# SCH_ESP32-Radio_2026-02-18.net
KiCad netlist of a schematic drawn in EasyEDA
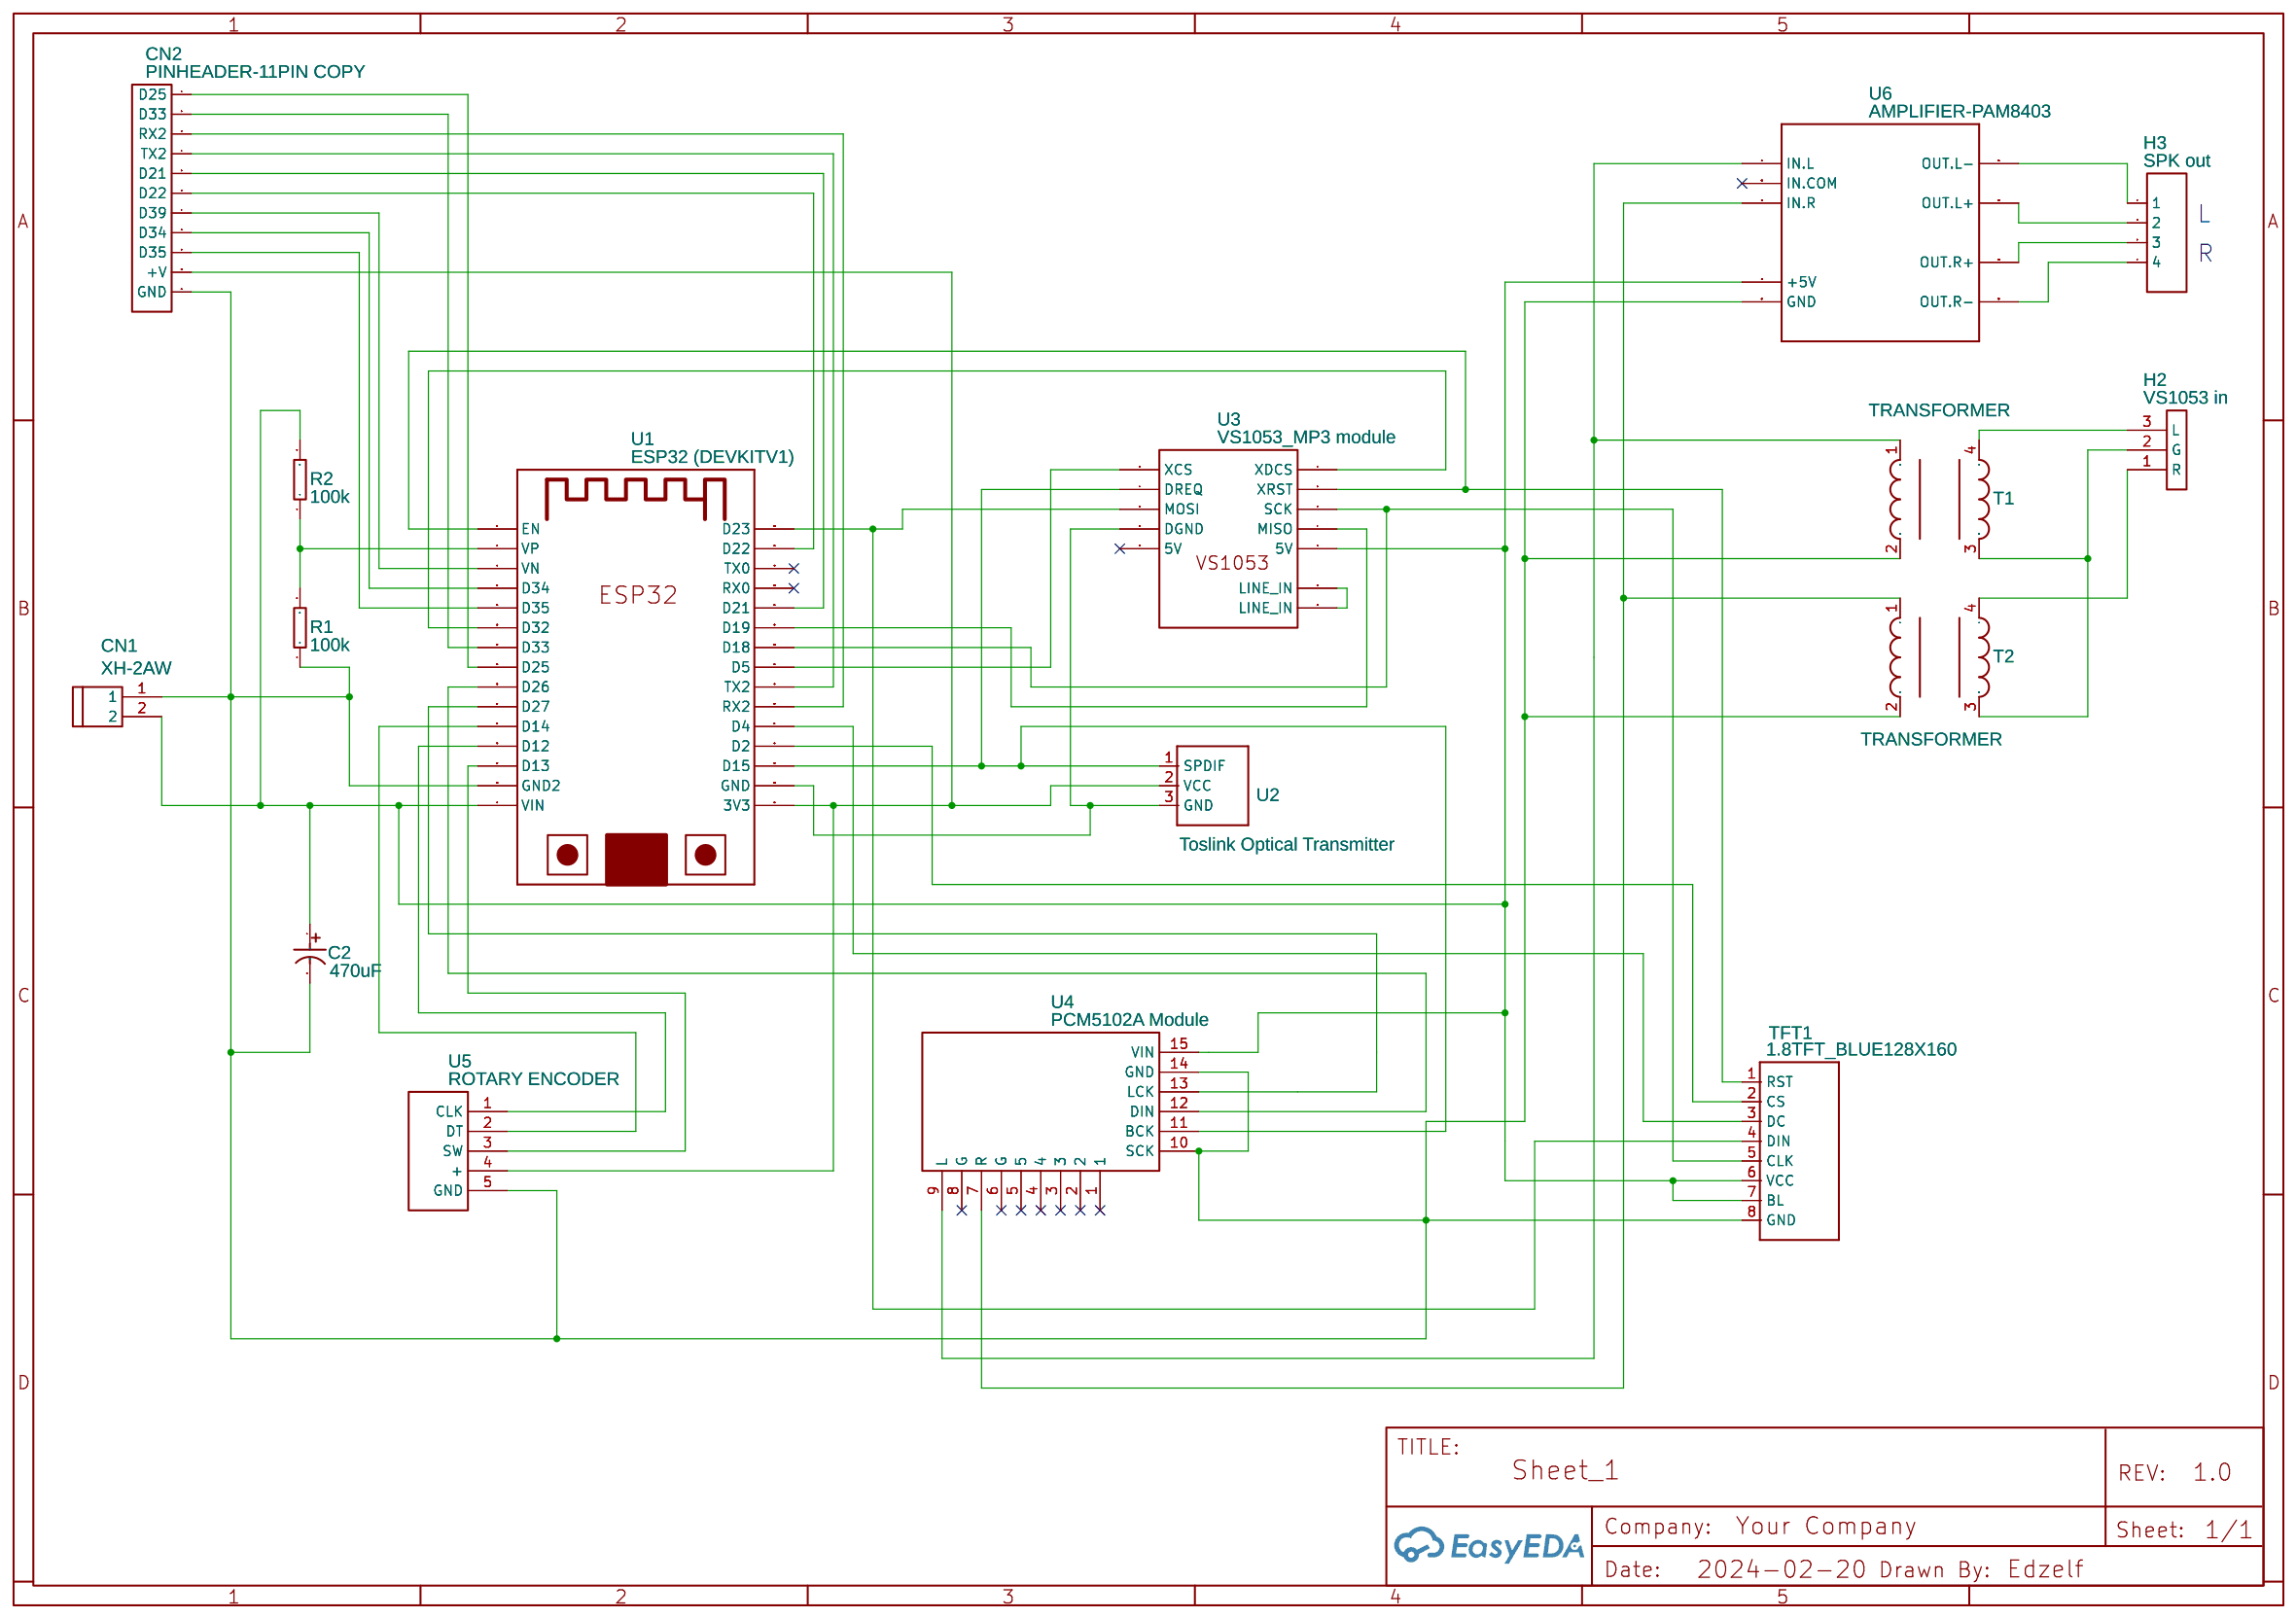
[diagram p0: schematic sheet]

(export (version "E")
  (design (tool "Eeschema 10.0.6"))
  (components
    (comp (ref "C2")
      (value "470uF")
      (fields (field (name "Manufacturer Part") "470uF 25V 8*14") (field (name "Manufacturer") "ValuePro"))
      (libsource (lib "") (part "470UF 25V 8X14"))
    )
    (comp (ref "CN1")
      (value "XH-2AW")
      (fields (field (name "Manufacturer") "BOOMELE(博穆精密)"))
      (libsource (lib "") (part "XH-2AW"))
    )
    (comp (ref "CN2") (value "PINHEADER-11PIN COPY") (libsource (lib "") (part "PINHEADER-11PIN COPY")))
    (comp (ref "H2") (value "VS1053 in") (libsource (lib "") (part "Pins_header1*3")))
    (comp (ref "H3")
      (value "SPK out")
      (fields
        (field (name "Manufacturer Part") "Female headerHDR1X8-2.54")
        (field (name "Manufacturer") "BOOMELE")
      )
      (libsource (lib "") (part "HEADER 4 PINS"))
    )
    (comp (ref "R1") (value "100k") (libsource (lib "") (part "Resistor 0.5W")))
    (comp (ref "R2") (value "100k") (libsource (lib "") (part "Resistor 0.5W")))
    (comp (ref "T1") (value "TRANSFORMER") (libsource (lib "") (part "TRANSFORMER")))
    (comp (ref "T2") (value "TRANSFORMER") (libsource (lib "") (part "TRANSFORMER")))
    (comp (ref "TFT1") (value "1.8TFT_BLUE128X160") (libsource (lib "") (part "1.8TFT_BLUE128X160")))
    (comp (ref "U1") (value "ESP32 (DEVKITV1)") (libsource (lib "") (part "ESP32-DEVKIT-V1-30PIN")))
    (comp (ref "U2")
      (value "Toslink Optical Transmitter")
      (fields (field (name "Manufacturer Part") "TOTX178A") (field (name "Manufacturer") "Toshiba"))
      (libsource (lib "") (part "TOTX178A Toslink Optical Transmitter"))
    )
    (comp (ref "U3")
      (value "VS1053_MP3 module")
      (fields (field (name "Manufacturer Part") "VS1053"))
      (libsource (lib "") (part "VS1053_MODULO_MP3"))
    )
    (comp (ref "U4") (value "PCM5102A Module") (libsource (lib "") (part "PCM5102A Module")))
    (comp (ref "U5") (value "ROTARY ENCODER") (libsource (lib "") (part "ROTARY ENCODER")))
    (comp (ref "U6") (value "AMPLIFIER-PAM8403") (libsource (lib "") (part "AMPLIFIER-PAM8403 COPY COPY")))
  )
  (nets
    (net (code "1") (name "Net-(CN2-+V)") (class "Default")
      (node (ref "CN2") (pin "10") (pinfunction "+V_10") (pintype "unspecified"))
      (node (ref "U1") (pin "3V3") (pinfunction "3V3_3V3") (pintype "unspecified"))
      (node (ref "U2") (pin "2") (pinfunction "VCC_2") (pintype "bidirectional"))
      (node (ref "U5") (pin "4") (pinfunction "+_4") (pintype "unspecified"))
    )
    (net (code "2") (name "Net-(CN2-D21)") (class "Default")
      (node (ref "CN2") (pin "5") (pinfunction "D21_5") (pintype "unspecified"))
      (node (ref "U1") (pin "D21") (pinfunction "D21_D21") (pintype "unspecified"))
    )
    (net (code "3") (name "Net-(CN2-D22)") (class "Default")
      (node (ref "CN2") (pin "6") (pinfunction "D22_6") (pintype "unspecified"))
      (node (ref "U1") (pin "D22") (pinfunction "D22_D22") (pintype "unspecified"))
    )
    (net (code "4") (name "Net-(CN2-D25)") (class "Default")
      (node (ref "CN2") (pin "1") (pinfunction "D25_1") (pintype "unspecified"))
      (node (ref "U1") (pin "D25") (pinfunction "D25_D25") (pintype "unspecified"))
    )
    (net (code "5") (name "Net-(CN2-D33)") (class "Default")
      (node (ref "CN2") (pin "2") (pinfunction "D33_2") (pintype "unspecified"))
      (node (ref "U1") (pin "D33") (pinfunction "D33_D33") (pintype "unspecified"))
    )
    (net (code "6") (name "Net-(CN2-D34)") (class "Default")
      (node (ref "CN2") (pin "8") (pinfunction "D34_8") (pintype "unspecified"))
      (node (ref "U1") (pin "D34") (pinfunction "D34_D34") (pintype "unspecified"))
    )
    (net (code "7") (name "Net-(CN2-D35)") (class "Default")
      (node (ref "CN2") (pin "9") (pinfunction "D35_9") (pintype "unspecified"))
      (node (ref "U1") (pin "D35") (pinfunction "D35_D35") (pintype "unspecified"))
    )
    (net (code "8") (name "Net-(CN2-D39)") (class "Default")
      (node (ref "CN2") (pin "7") (pinfunction "D39_7") (pintype "unspecified"))
      (node (ref "U1") (pin "VN") (pinfunction "VN_VN") (pintype "unspecified"))
    )
    (net (code "9") (name "Net-(CN2-GND)") (class "Default")
      (node (ref "C2") (pin "2") (pinfunction "2_2") (pintype "input"))
      (node (ref "CN1") (pin "1") (pinfunction "1_1") (pintype "unspecified"))
      (node (ref "CN2") (pin "11") (pinfunction "GND_11") (pintype "unspecified"))
      (node (ref "R1") (pin "1") (pinfunction "1_1") (pintype "unspecified"))
      (node (ref "T1") (pin "2") (pinfunction "2_2") (pintype "unspecified"))
      (node (ref "T2") (pin "2") (pinfunction "2_2") (pintype "unspecified"))
      (node (ref "TFT1") (pin "8") (pinfunction "GND_8") (pintype "bidirectional"))
      (node (ref "U1") (pin "GND2") (pinfunction "GND2_GND2") (pintype "unspecified"))
      (node (ref "U4") (pin "10") (pinfunction "SCK_10") (pintype "unspecified"))
      (node (ref "U4") (pin "14") (pinfunction "GND_14") (pintype "unspecified"))
      (node (ref "U5") (pin "5") (pinfunction "GND_5") (pintype "unspecified"))
      (node (ref "U6") (pin "GND") (pinfunction "GND_GND") (pintype "passive"))
    )
    (net (code "10") (name "Net-(CN2-RX2)") (class "Default")
      (node (ref "CN2") (pin "3") (pinfunction "RX2_3") (pintype "unspecified"))
      (node (ref "U1") (pin "RX2") (pinfunction "RX2_RX2") (pintype "unspecified"))
    )
    (net (code "11") (name "Net-(CN2-TX2)") (class "Default")
      (node (ref "CN2") (pin "4") (pinfunction "TX2_4") (pintype "unspecified"))
      (node (ref "U1") (pin "TX2") (pinfunction "TX2_TX2") (pintype "unspecified"))
    )
    (net (code "12") (name "Net-(H2-G)") (class "Default")
      (node (ref "H2") (pin "2") (pinfunction "G_2") (pintype "unspecified"))
      (node (ref "T1") (pin "3") (pinfunction "3_3") (pintype "unspecified"))
      (node (ref "T2") (pin "3") (pinfunction "3_3") (pintype "unspecified"))
    )
    (net (code "13") (name "Net-(H2-L)") (class "Default")
      (node (ref "H2") (pin "3") (pinfunction "L_3") (pintype "unspecified"))
      (node (ref "T1") (pin "4") (pinfunction "4_4") (pintype "unspecified"))
    )
    (net (code "14") (name "Net-(H2-R)") (class "Default")
      (node (ref "H2") (pin "1") (pinfunction "R_1") (pintype "unspecified"))
      (node (ref "T2") (pin "4") (pinfunction "4_4") (pintype "unspecified"))
    )
    (net (code "15") (name "Net-(H3-Pad1)") (class "Default")
      (node (ref "H3") (pin "1") (pinfunction "1_1") (pintype "unspecified"))
      (node (ref "U6") (pin "OUT.L-") (pinfunction "OUT.L-_OUT.L-") (pintype "output"))
    )
    (net (code "16") (name "Net-(H3-Pad2)") (class "Default")
      (node (ref "H3") (pin "2") (pinfunction "2_2") (pintype "unspecified"))
      (node (ref "U6") (pin "OUT.L+") (pinfunction "OUT.L+_OUT.L+") (pintype "output"))
    )
    (net (code "17") (name "Net-(H3-Pad3)") (class "Default")
      (node (ref "H3") (pin "3") (pinfunction "3_3") (pintype "unspecified"))
      (node (ref "U6") (pin "OUT.R+") (pinfunction "OUT.R+_OUT.R+") (pintype "output"))
    )
    (net (code "18") (name "Net-(H3-Pad4)") (class "Default")
      (node (ref "H3") (pin "4") (pinfunction "4_4") (pintype "unspecified"))
      (node (ref "U6") (pin "OUT.R-") (pinfunction "OUT.R-_OUT.R-") (pintype "output"))
    )
    (net (code "19") (name "Net-(R1-Pad2)") (class "Default")
      (node (ref "R1") (pin "2") (pinfunction "2_2") (pintype "unspecified"))
      (node (ref "R2") (pin "1") (pinfunction "1_1") (pintype "unspecified"))
      (node (ref "U1") (pin "VP") (pinfunction "VP_VP") (pintype "unspecified"))
    )
    (net (code "20") (name "Net-(TFT1-BL)") (class "Default")
      (node (ref "C2") (pin "1") (pinfunction "1_1") (pintype "input"))
      (node (ref "CN1") (pin "2") (pinfunction "2_2") (pintype "unspecified"))
      (node (ref "R2") (pin "2") (pinfunction "2_2") (pintype "unspecified"))
      (node (ref "TFT1") (pin "6") (pinfunction "VCC_6") (pintype "bidirectional"))
      (node (ref "TFT1") (pin "7") (pinfunction "BL_7") (pintype "bidirectional"))
      (node (ref "U1") (pin "VIN") (pinfunction "VIN_VIN") (pintype "unspecified"))
      (node (ref "U3") (pin "9") (pinfunction "5V_9") (pintype "bidirectional"))
      (node (ref "U4") (pin "15") (pinfunction "VIN_15") (pintype "unspecified"))
      (node (ref "U6") (pin "+5V") (pinfunction "+5V_+5V") (pintype "passive"))
    )
    (net (code "21") (name "Net-(TFT1-CLK)") (class "Default")
      (node (ref "TFT1") (pin "5") (pinfunction "CLK_5") (pintype "bidirectional"))
      (node (ref "U1") (pin "D18") (pinfunction "D18_D18") (pintype "unspecified"))
      (node (ref "U3") (pin "5") (pinfunction "SCK_5") (pintype "bidirectional"))
    )
    (net (code "22") (name "Net-(TFT1-CS)") (class "Default")
      (node (ref "TFT1") (pin "2") (pinfunction "CS_2") (pintype "bidirectional"))
      (node (ref "U1") (pin "D2") (pinfunction "D2_D2") (pintype "unspecified"))
    )
    (net (code "23") (name "Net-(TFT1-DC)") (class "Default")
      (node (ref "TFT1") (pin "3") (pinfunction "DC_3") (pintype "bidirectional"))
      (node (ref "U1") (pin "D4") (pinfunction "D4_D4") (pintype "unspecified"))
    )
    (net (code "24") (name "Net-(TFT1-DIN)") (class "Default")
      (node (ref "TFT1") (pin "4") (pinfunction "DIN_4") (pintype "bidirectional"))
      (node (ref "U1") (pin "D23") (pinfunction "D23_D23") (pintype "unspecified"))
      (node (ref "U3") (pin "6") (pinfunction "MOSI_6") (pintype "bidirectional"))
    )
    (net (code "25") (name "Net-(TFT1-RST)") (class "Default")
      (node (ref "TFT1") (pin "1") (pinfunction "RST_1") (pintype "bidirectional"))
      (node (ref "U1") (pin "EN") (pinfunction "EN_EN") (pintype "unspecified"))
      (node (ref "U3") (pin "3") (pinfunction "XRST_3") (pintype "bidirectional"))
    )
    (net (code "26") (name "Net-(U2-GND)") (class "Default")
      (node (ref "U1") (pin "GND") (pinfunction "GND_GND") (pintype "unspecified"))
      (node (ref "U2") (pin "3") (pinfunction "GND_3") (pintype "bidirectional"))
      (node (ref "U3") (pin "8") (pinfunction "DGND_8") (pintype "bidirectional"))
    )
    (net (code "27") (name "Net-(U2-SPDIF)") (class "Default")
      (node (ref "U1") (pin "D15") (pinfunction "D15_D15") (pintype "unspecified"))
      (node (ref "U2") (pin "1") (pinfunction "SPDIF_1") (pintype "bidirectional"))
      (node (ref "U3") (pin "4") (pinfunction "DREQ_4") (pintype "bidirectional"))
      (node (ref "U4") (pin "11") (pinfunction "BCK_11") (pintype "unspecified"))
    )
    (net (code "28") (name "Net-(U3-LINE_IN-Pad11)") (class "Default")
      (node (ref "U3") (pin "11") (pinfunction "LINE_IN_11") (pintype "bidirectional"))
      (node (ref "U3") (pin "12") (pinfunction "LINE_IN_12") (pintype "bidirectional"))
    )
    (net (code "29") (name "Net-(U3-MISO)") (class "Default")
      (node (ref "U1") (pin "D19") (pinfunction "D19_D19") (pintype "unspecified"))
      (node (ref "U3") (pin "7") (pinfunction "MISO_7") (pintype "bidirectional"))
    )
    (net (code "30") (name "Net-(U3-XCS)") (class "Default")
      (node (ref "U1") (pin "D5") (pinfunction "D5_D5") (pintype "unspecified"))
      (node (ref "U3") (pin "2") (pinfunction "XCS_2") (pintype "bidirectional"))
    )
    (net (code "31") (name "Net-(U3-XDCS)") (class "Default")
      (node (ref "U1") (pin "D32") (pinfunction "D32_D32") (pintype "unspecified"))
      (node (ref "U3") (pin "1") (pinfunction "XDCS_1") (pintype "bidirectional"))
    )
    (net (code "32") (name "Net-(U4-DIN)") (class "Default")
      (node (ref "U1") (pin "D26") (pinfunction "D26_D26") (pintype "unspecified"))
      (node (ref "U4") (pin "12") (pinfunction "DIN_12") (pintype "unspecified"))
    )
    (net (code "33") (name "Net-(U4-L)") (class "Default")
      (node (ref "T1") (pin "1") (pinfunction "1_1") (pintype "unspecified"))
      (node (ref "U4") (pin "9") (pinfunction "L_9") (pintype "unspecified"))
      (node (ref "U6") (pin "IN.L") (pinfunction "IN.L_IN.L") (pintype "input"))
    )
    (net (code "34") (name "Net-(U4-LCK)") (class "Default")
      (node (ref "U1") (pin "D27") (pinfunction "D27_D27") (pintype "unspecified"))
      (node (ref "U4") (pin "13") (pinfunction "LCK_13") (pintype "unspecified"))
    )
    (net (code "35") (name "Net-(U4-R)") (class "Default")
      (node (ref "T2") (pin "1") (pinfunction "1_1") (pintype "unspecified"))
      (node (ref "U4") (pin "7") (pinfunction "R_7") (pintype "unspecified"))
      (node (ref "U6") (pin "IN.R") (pinfunction "IN.R_IN.R") (pintype "unspecified"))
    )
    (net (code "36") (name "Net-(U5-CLK)") (class "Default")
      (node (ref "U1") (pin "D12") (pinfunction "D12_D12") (pintype "unspecified"))
      (node (ref "U5") (pin "1") (pinfunction "CLK_1") (pintype "unspecified"))
    )
    (net (code "37") (name "Net-(U5-DT)") (class "Default")
      (node (ref "U1") (pin "D14") (pinfunction "D14_D14") (pintype "unspecified"))
      (node (ref "U5") (pin "2") (pinfunction "DT_2") (pintype "unspecified"))
    )
    (net (code "38") (name "Net-(U5-SW)") (class "Default")
      (node (ref "U1") (pin "D13") (pinfunction "D13_D13") (pintype "unspecified"))
      (node (ref "U5") (pin "3") (pinfunction "SW_3") (pintype "unspecified"))
    )
    (net (code "39") (name "unconnected-(U1-PadRX0)") (class "Default")
      (node (ref "U1") (pin "RX0") (pinfunction "RX0_RX0") (pintype "unspecified+no_connect"))
    )
    (net (code "40") (name "unconnected-(U1-PadTX0)") (class "Default")
      (node (ref "U1") (pin "TX0") (pinfunction "TX0_TX0") (pintype "unspecified+no_connect"))
    )
    (net (code "41") (name "unconnected-(U3-5V-Pad10)") (class "Default")
      (node (ref "U3") (pin "10") (pinfunction "5V_10") (pintype "bidirectional+no_connect"))
    )
    (net (code "42") (name "unconnected-(U4-G-Pad6)") (class "Default")
      (node (ref "U4") (pin "6") (pinfunction "G_6") (pintype "unspecified+no_connect"))
    )
    (net (code "43") (name "unconnected-(U4-G-Pad8)") (class "Default")
      (node (ref "U4") (pin "8") (pinfunction "G_8") (pintype "unspecified+no_connect"))
    )
    (net (code "44") (name "unconnected-(U4-Pad1)") (class "Default")
      (node (ref "U4") (pin "1") (pinfunction "1_1") (pintype "unspecified+no_connect"))
    )
    (net (code "45") (name "unconnected-(U4-Pad2)") (class "Default")
      (node (ref "U4") (pin "2") (pinfunction "2_2") (pintype "unspecified+no_connect"))
    )
    (net (code "46") (name "unconnected-(U4-Pad3)") (class "Default")
      (node (ref "U4") (pin "3") (pinfunction "3_3") (pintype "unspecified+no_connect"))
    )
    (net (code "47") (name "unconnected-(U4-Pad4)") (class "Default")
      (node (ref "U4") (pin "4") (pinfunction "4_4") (pintype "unspecified+no_connect"))
    )
    (net (code "48") (name "unconnected-(U4-Pad5)") (class "Default")
      (node (ref "U4") (pin "5") (pinfunction "5_5") (pintype "unspecified+no_connect"))
    )
    (net (code "49") (name "unconnected-(U6-PadIN.COM)") (class "Default")
      (node (ref "U6") (pin "IN.COM") (pinfunction "IN.COM_IN.COM") (pintype "input+no_connect"))
    )
  )
)
